# EnDat.net
KiCad netlist of a schematic drawn in Altium Designer
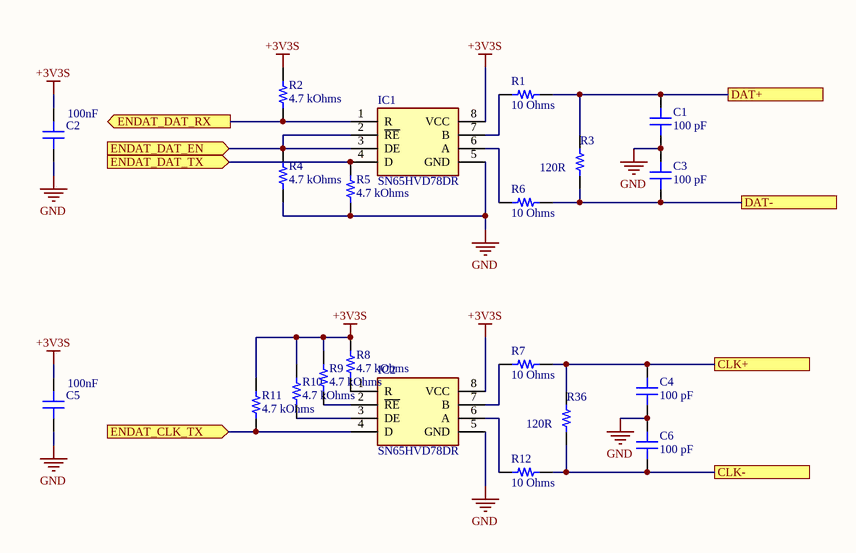
[diagram p0: EnDat.SchDoc]

(export (version "E")
  (design (tool "Eeschema 10.0.6"))
  (components
    (comp (ref "C1")
      (value "100 pF")
      (footprint "CAP 0402_1005")
      (description "CAP CER 100PF 50V C0G/NP0 0402")
      (fields
        (field (name "PART NUMBER") "500X07N101MV4T")
        (field (name "CAPACITANCE") "100 pF")
        (field (name "MANUFACTURER") "Johanson Dielectrics Inc.")
      )
      (libsource (lib "Celestial Altium Library - altium_library") (part "Capacitor"))
    )
    (comp (ref "C2")
      (value "100nF")
      (footprint "CAP 0402_1005")
      (description "CAP CER 1UF 16V X5R 0402")
      (fields (field (name "PART NUMBER") "C29266") (field (name "MANUFACTURER") "Samsung Electro-Mechanics"))
      (libsource (lib "Celestial Altium Library - altium_library") (part "Capacitor"))
    )
    (comp (ref "C3")
      (value "100 pF")
      (footprint "CAP 0402_1005")
      (description "CAP CER 100PF 50V C0G/NP0 0402")
      (fields
        (field (name "PART NUMBER") "500X07N101MV4T")
        (field (name "CAPACITANCE") "100 pF")
        (field (name "MANUFACTURER") "Johanson Dielectrics Inc.")
      )
      (libsource (lib "Celestial Altium Library - altium_library") (part "Capacitor"))
    )
    (comp (ref "C4")
      (value "100 pF")
      (footprint "CAP 0402_1005")
      (description "CAP CER 100PF 50V C0G/NP0 0402")
      (fields
        (field (name "PART NUMBER") "500X07N101MV4T")
        (field (name "CAPACITANCE") "100 pF")
        (field (name "MANUFACTURER") "Johanson Dielectrics Inc.")
      )
      (libsource (lib "Celestial Altium Library - altium_library") (part "Capacitor"))
    )
    (comp (ref "C5")
      (value "100nF")
      (footprint "CAP 0402_1005")
      (description "CAP CER 1UF 16V X5R 0402")
      (fields (field (name "PART NUMBER") "C29266") (field (name "MANUFACTURER") "Samsung Electro-Mechanics"))
      (libsource (lib "Celestial Altium Library - altium_library") (part "Capacitor"))
    )
    (comp (ref "C6")
      (value "100 pF")
      (footprint "CAP 0402_1005")
      (description "CAP CER 100PF 50V C0G/NP0 0402")
      (fields
        (field (name "PART NUMBER") "500X07N101MV4T")
        (field (name "CAPACITANCE") "100 pF")
        (field (name "MANUFACTURER") "Johanson Dielectrics Inc.")
      )
      (libsource (lib "Celestial Altium Library - altium_library") (part "Capacitor"))
    )
    (comp (ref "IC1")
      (value "SN65HVD78DR")
      (footprint "SOIC127P600X175-8N")
      (description "Integrated Circuit")
      (fields (field (name "MOUSER PART NUMBER") "595-SN65HVD78DR"))
      (libsource (lib "Schlib1") (part "SN65HVD78DR"))
    )
    (comp (ref "IC2")
      (value "SN65HVD78DR")
      (footprint "SOIC127P600X175-8N")
      (description "Integrated Circuit")
      (fields (field (name "MOUSER PART NUMBER") "595-SN65HVD78DR"))
      (libsource (lib "Schlib1") (part "SN65HVD78DR"))
    )
    (comp (ref "R1")
      (value "10 Ohms")
      (footprint "RES 0402_1005")
      (description "RES 10 OHM 5% 1/16W 0402")
      (fields
        (field (name "PART NUMBER") "WR04X100 JTL")
        (field (name "MANUFACTURER") "Walsin Technology Corporation")
      )
      (libsource (lib "Celestial Altium Library - altium_library") (part "Resistor"))
    )
    (comp (ref "R2")
      (value "4.7 kOhms")
      (footprint "RES 0402_1005")
      (description "RES 4.7K OHM 1% 1/16W 0402")
      (fields
        (field (name "PART NUMBER") "WR04X4701FTL")
        (field (name "MANUFACTURER") "Walsin Technology Corporation")
      )
      (libsource (lib "Celestial Altium Library - altium_library") (part "Resistor"))
    )
    (comp (ref "R3")
      (value "120R")
      (footprint "RES 0603_1608")
      (description "RESA-AS 0603 10R 1% 100MW TC100")
      (fields (field (name "PART NUMBER") "CR0603AFX-10R0EAS") (field (name "MANUFACTURER") "Bourns Inc."))
      (libsource (lib "Celestial Altium Library - altium_library") (part "Resistor"))
    )
    (comp (ref "R4")
      (value "4.7 kOhms")
      (footprint "RES 0402_1005")
      (description "RES 4.7K OHM 1% 1/16W 0402")
      (fields
        (field (name "PART NUMBER") "WR04X4701FTL")
        (field (name "MANUFACTURER") "Walsin Technology Corporation")
      )
      (libsource (lib "Celestial Altium Library - altium_library") (part "Resistor"))
    )
    (comp (ref "R5")
      (value "4.7 kOhms")
      (footprint "RES 0402_1005")
      (description "RES 4.7K OHM 1% 1/16W 0402")
      (fields
        (field (name "PART NUMBER") "WR04X4701FTL")
        (field (name "MANUFACTURER") "Walsin Technology Corporation")
      )
      (libsource (lib "Celestial Altium Library - altium_library") (part "Resistor"))
    )
    (comp (ref "R6")
      (value "10 Ohms")
      (footprint "RES 0402_1005")
      (description "RES 10 OHM 5% 1/16W 0402")
      (fields
        (field (name "PART NUMBER") "WR04X100 JTL")
        (field (name "MANUFACTURER") "Walsin Technology Corporation")
      )
      (libsource (lib "Celestial Altium Library - altium_library") (part "Resistor"))
    )
    (comp (ref "R7")
      (value "10 Ohms")
      (footprint "RES 0402_1005")
      (description "RES 10 OHM 5% 1/16W 0402")
      (fields
        (field (name "PART NUMBER") "WR04X100 JTL")
        (field (name "MANUFACTURER") "Walsin Technology Corporation")
      )
      (libsource (lib "Celestial Altium Library - altium_library") (part "Resistor"))
    )
    (comp (ref "R8")
      (value "4.7 kOhms")
      (footprint "RES 0402_1005")
      (description "RES 4.7K OHM 1% 1/16W 0402")
      (fields
        (field (name "PART NUMBER") "WR04X4701FTL")
        (field (name "MANUFACTURER") "Walsin Technology Corporation")
      )
      (libsource (lib "Celestial Altium Library - altium_library") (part "Resistor"))
    )
    (comp (ref "R9")
      (value "4.7 kOhms")
      (footprint "RES 0402_1005")
      (description "RES 4.7K OHM 1% 1/16W 0402")
      (fields
        (field (name "PART NUMBER") "WR04X4701FTL")
        (field (name "MANUFACTURER") "Walsin Technology Corporation")
      )
      (libsource (lib "Celestial Altium Library - altium_library") (part "Resistor"))
    )
    (comp (ref "R10")
      (value "4.7 kOhms")
      (footprint "RES 0402_1005")
      (description "RES 4.7K OHM 1% 1/16W 0402")
      (fields
        (field (name "PART NUMBER") "WR04X4701FTL")
        (field (name "MANUFACTURER") "Walsin Technology Corporation")
      )
      (libsource (lib "Celestial Altium Library - altium_library") (part "Resistor"))
    )
    (comp (ref "R11")
      (value "4.7 kOhms")
      (footprint "RES 0402_1005")
      (description "RES 4.7K OHM 1% 1/16W 0402")
      (fields
        (field (name "PART NUMBER") "WR04X4701FTL")
        (field (name "MANUFACTURER") "Walsin Technology Corporation")
      )
      (libsource (lib "Celestial Altium Library - altium_library") (part "Resistor"))
    )
    (comp (ref "R12")
      (value "10 Ohms")
      (footprint "RES 0402_1005")
      (description "RES 10 OHM 5% 1/16W 0402")
      (fields
        (field (name "PART NUMBER") "WR04X100 JTL")
        (field (name "MANUFACTURER") "Walsin Technology Corporation")
      )
      (libsource (lib "Celestial Altium Library - altium_library") (part "Resistor"))
    )
    (comp (ref "R36")
      (value "120R")
      (footprint "RES 0603_1608")
      (description "RESA-AS 0603 10R 1% 100MW TC100")
      (fields (field (name "PART NUMBER") "CR0603AFX-10R0EAS") (field (name "MANUFACTURER") "Bourns Inc."))
      (libsource (lib "Celestial Altium Library - altium_library") (part "Resistor"))
    )
  )
  (nets
    (net (code "1") (name "+3V3S") (class "Default")
      (node (ref "C2") (pin "2") (pinfunction "2_2") (pintype "passive"))
      (node (ref "C5") (pin "2") (pinfunction "2_2") (pintype "passive"))
      (node (ref "IC1") (pin "8") (pinfunction "VCC_8") (pintype "passive"))
      (node (ref "IC2") (pin "8") (pinfunction "VCC_8") (pintype "passive"))
      (node (ref "R10") (pin "2") (pinfunction "2_2") (pintype "passive"))
      (node (ref "R11") (pin "2") (pinfunction "2_2") (pintype "passive"))
      (node (ref "R2") (pin "2") (pinfunction "2_2") (pintype "passive"))
      (node (ref "R8") (pin "2") (pinfunction "2_2") (pintype "passive"))
      (node (ref "R9") (pin "2") (pinfunction "2_2") (pintype "passive"))
    )
    (net (code "2") (name "/CLK+") (class "Default")
      (node (ref "C4") (pin "2") (pinfunction "2_2") (pintype "passive"))
      (node (ref "R36") (pin "2") (pinfunction "2_2") (pintype "passive"))
      (node (ref "R7") (pin "2") (pinfunction "2_2") (pintype "passive"))
    )
    (net (code "3") (name "/CLK-") (class "Default")
      (node (ref "C6") (pin "1") (pinfunction "1_1") (pintype "passive"))
      (node (ref "R12") (pin "2") (pinfunction "2_2") (pintype "passive"))
      (node (ref "R36") (pin "1") (pinfunction "1_1") (pintype "passive"))
    )
    (net (code "4") (name "/DAT+") (class "Default")
      (node (ref "C1") (pin "2") (pinfunction "2_2") (pintype "passive"))
      (node (ref "R1") (pin "2") (pinfunction "2_2") (pintype "passive"))
      (node (ref "R3") (pin "2") (pinfunction "2_2") (pintype "passive"))
    )
    (net (code "5") (name "/DAT-") (class "Default")
      (node (ref "C3") (pin "1") (pinfunction "1_1") (pintype "passive"))
      (node (ref "R3") (pin "1") (pinfunction "1_1") (pintype "passive"))
      (node (ref "R6") (pin "2") (pinfunction "2_2") (pintype "passive"))
    )
    (net (code "6") (name "/ENDAT_CLK_TX") (class "Default")
      (node (ref "IC2") (pin "4") (pinfunction "D_4") (pintype "passive"))
      (node (ref "R11") (pin "1") (pinfunction "1_1") (pintype "passive"))
    )
    (net (code "7") (name "/ENDAT_DAT_EN") (class "Default")
      (node (ref "IC1") (pin "2") (pinfunction "~{RE}_2") (pintype "passive"))
      (node (ref "IC1") (pin "3") (pinfunction "DE_3") (pintype "passive"))
      (node (ref "R4") (pin "2") (pinfunction "2_2") (pintype "passive"))
    )
    (net (code "8") (name "/ENDAT_DAT_RX") (class "Default")
      (node (ref "IC1") (pin "1") (pinfunction "R_1") (pintype "passive"))
      (node (ref "R2") (pin "1") (pinfunction "1_1") (pintype "passive"))
    )
    (net (code "9") (name "/ENDAT_DAT_TX") (class "Default")
      (node (ref "IC1") (pin "4") (pinfunction "D_4") (pintype "passive"))
      (node (ref "R5") (pin "2") (pinfunction "2_2") (pintype "passive"))
    )
    (net (code "10") (name "GND") (class "Default")
      (node (ref "C1") (pin "1") (pinfunction "1_1") (pintype "passive"))
      (node (ref "C2") (pin "1") (pinfunction "1_1") (pintype "passive"))
      (node (ref "C3") (pin "2") (pinfunction "2_2") (pintype "passive"))
      (node (ref "C4") (pin "1") (pinfunction "1_1") (pintype "passive"))
      (node (ref "C5") (pin "1") (pinfunction "1_1") (pintype "passive"))
      (node (ref "C6") (pin "2") (pinfunction "2_2") (pintype "passive"))
      (node (ref "IC1") (pin "5") (pinfunction "GND_5") (pintype "passive"))
      (node (ref "IC2") (pin "5") (pinfunction "GND_5") (pintype "passive"))
      (node (ref "R4") (pin "1") (pinfunction "1_1") (pintype "passive"))
      (node (ref "R5") (pin "1") (pinfunction "1_1") (pintype "passive"))
    )
    (net (code "11") (name "Net-(IC1-A)") (class "Default")
      (node (ref "IC1") (pin "6") (pinfunction "A_6") (pintype "passive"))
      (node (ref "R6") (pin "1") (pinfunction "1_1") (pintype "passive"))
    )
    (net (code "12") (name "Net-(IC1-B)") (class "Default")
      (node (ref "IC1") (pin "7") (pinfunction "B_7") (pintype "passive"))
      (node (ref "R1") (pin "1") (pinfunction "1_1") (pintype "passive"))
    )
    (net (code "13") (name "Net-(IC2-A)") (class "Default")
      (node (ref "IC2") (pin "6") (pinfunction "A_6") (pintype "passive"))
      (node (ref "R12") (pin "1") (pinfunction "1_1") (pintype "passive"))
    )
    (net (code "14") (name "Net-(IC2-B)") (class "Default")
      (node (ref "IC2") (pin "7") (pinfunction "B_7") (pintype "passive"))
      (node (ref "R7") (pin "1") (pinfunction "1_1") (pintype "passive"))
    )
    (net (code "15") (name "Net-(IC2-DE)") (class "Default")
      (node (ref "IC2") (pin "3") (pinfunction "DE_3") (pintype "passive"))
      (node (ref "R10") (pin "1") (pinfunction "1_1") (pintype "passive"))
    )
    (net (code "16") (name "Net-(IC2-R)") (class "Default")
      (node (ref "IC2") (pin "1") (pinfunction "R_1") (pintype "passive"))
      (node (ref "R8") (pin "1") (pinfunction "1_1") (pintype "passive"))
    )
    (net (code "17") (name "Net-(IC2-~{RE})") (class "Default")
      (node (ref "IC2") (pin "2") (pinfunction "~{RE}_2") (pintype "passive"))
      (node (ref "R9") (pin "1") (pinfunction "1_1") (pintype "passive"))
    )
  )
)
